# TC377TP_2.net
KiCad netlist of a schematic drawn in Altium Designer
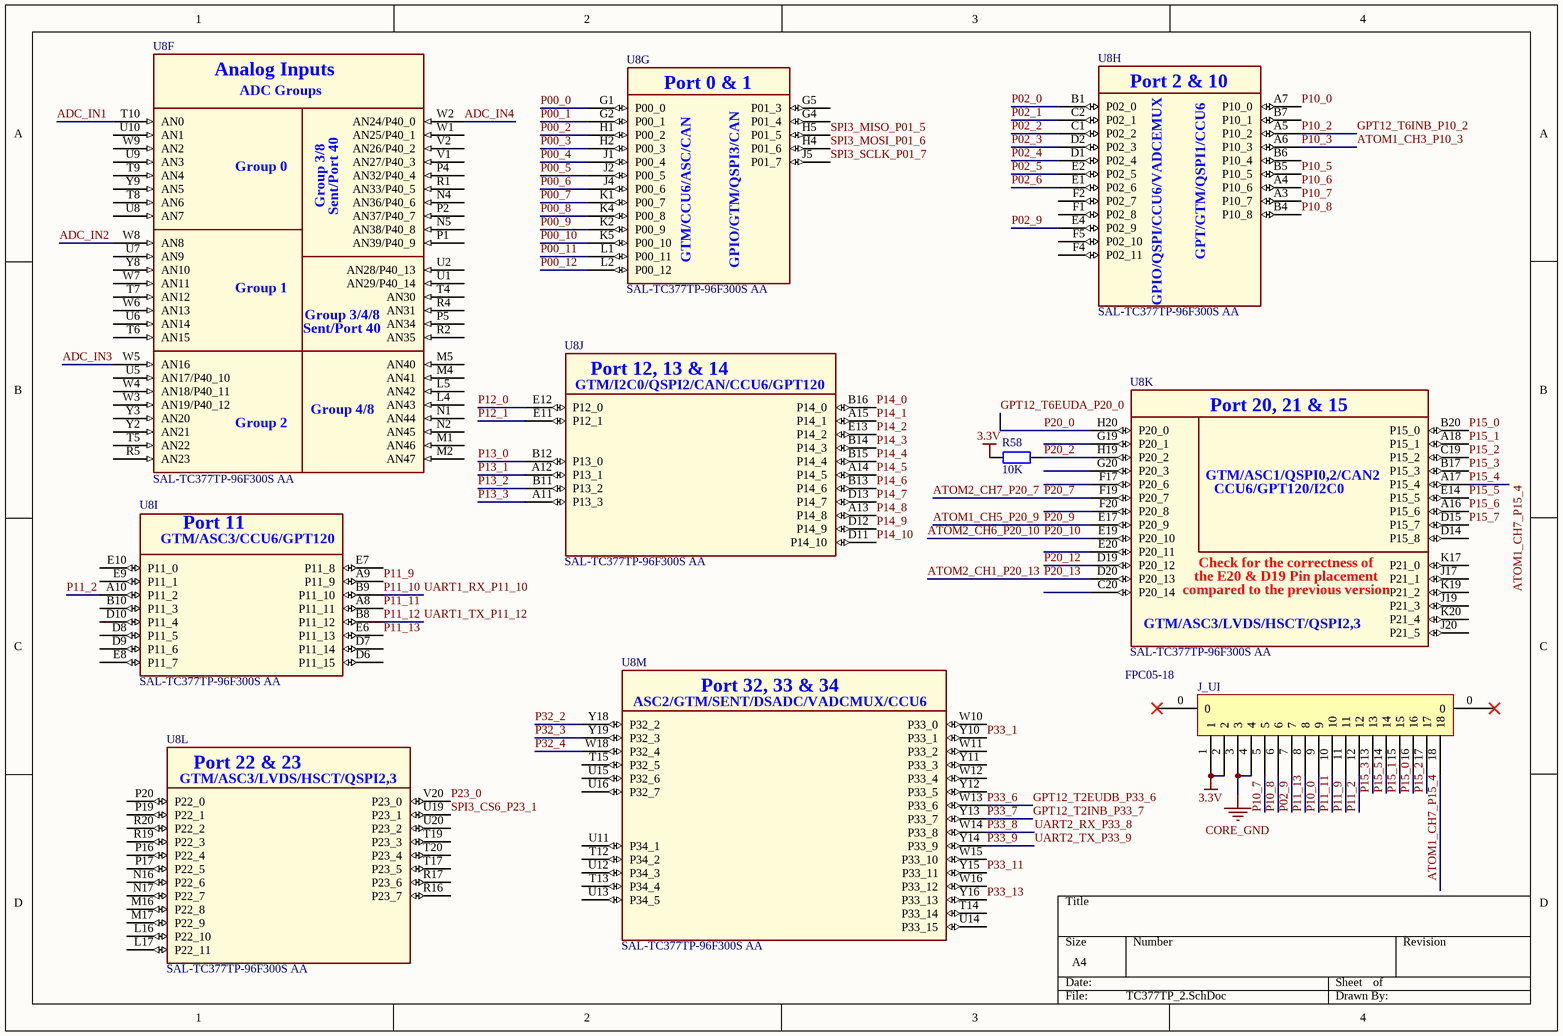
[diagram p0: TC377TP_2.SchDoc]

(export (version "E")
  (design (tool "Eeschema 10.0.6"))
  (components
    (comp (ref "J_UI")
      (value "FPC05-18")
      (footprint "FPC-05mm-18")
      (libsource (lib "FPC18") (part "FPC05-18"))
    )
    (comp (ref "R58")
      (value "10K")
      (footprint "R 0603_L")
      (description "贴片电阻")
      (fields (field (name "版权归属") "源创客"))
      (libsource (lib "3.1   - 电阻-电容-电感") (part "R"))
    )
    (comp (ref "U8")
      (value "SAL-TC377TP-96F300S AA")
      (footprint "BGA292C80P20X20")
      (description "32-Bit Single-Chip Microcontroller")
      (fields (field (name "MANUFACTURER") "Infineon Technologies"))
      (libsource (lib "SAL-TC377TP-96F300S AA") (part "SAL-TC377TP-96F300S AA"))
    )
  )
  (nets
    (net (code "1") (name "/ADC_IN1") (class "Default")
      (node (ref "U8") (pin "T10") (pinfunction "AN0_T10") (pintype "input"))
    )
    (net (code "2") (name "/ADC_IN2") (class "Default")
      (node (ref "U8") (pin "W8") (pinfunction "AN8_W8") (pintype "input"))
    )
    (net (code "3") (name "/ADC_IN3") (class "Default")
      (node (ref "U8") (pin "W5") (pinfunction "AN16_W5") (pintype "input"))
    )
    (net (code "4") (name "/ADC_IN4") (class "Default")
      (node (ref "U8") (pin "W2") (pinfunction "AN24/P40_0_W2") (pintype "input"))
    )
    (net (code "5") (name "/ATOM1_CH3_P10_3") (class "Default")
      (node (ref "U8") (pin "A6") (pinfunction "P10_3_A6") (pintype "bidirectional"))
    )
    (net (code "6") (name "/ATOM1_CH5_P20_9") (class "Default")
      (node (ref "U8") (pin "E17") (pinfunction "P20_9_E17") (pintype "bidirectional"))
    )
    (net (code "7") (name "/ATOM1_CH7_P15_4") (class "Default")
      (node (ref "J_UI") (pin "18") (pinfunction "18_18") (pintype "passive"))
      (node (ref "U8") (pin "A17") (pinfunction "P15_4_A17") (pintype "bidirectional"))
    )
    (net (code "8") (name "/ATOM2_CH1_P20_13") (class "Default")
      (node (ref "U8") (pin "D20") (pinfunction "P20_13_D20") (pintype "bidirectional"))
    )
    (net (code "9") (name "/ATOM2_CH6_P20_10") (class "Default")
      (node (ref "U8") (pin "E19") (pinfunction "P20_10_E19") (pintype "bidirectional"))
    )
    (net (code "10") (name "/ATOM2_CH7_P20_7") (class "Default")
      (node (ref "U8") (pin "F19") (pinfunction "P20_7_F19") (pintype "bidirectional"))
    )
    (net (code "11") (name "/GPT12_T2EUDB_P33_6") (class "Default")
      (node (ref "U8") (pin "W13") (pinfunction "P33_6_W13") (pintype "bidirectional"))
    )
    (net (code "12") (name "/GPT12_T2INB_P33_7") (class "Default")
      (node (ref "U8") (pin "Y13") (pinfunction "P33_7_Y13") (pintype "bidirectional"))
    )
    (net (code "13") (name "/GPT12_T6EUDA_P20_0") (class "Default")
      (node (ref "U8") (pin "H20") (pinfunction "P20_0_H20") (pintype "bidirectional"))
    )
    (net (code "14") (name "/GPT12_T6INB_P10_2") (class "Default")
      (node (ref "U8") (pin "A5") (pinfunction "P10_2_A5") (pintype "bidirectional"))
    )
    (net (code "15") (name "/P00_0") (class "Default")
      (node (ref "U8") (pin "G1") (pinfunction "P00_0_G1") (pintype "bidirectional"))
    )
    (net (code "16") (name "/P00_1") (class "Default")
      (node (ref "U8") (pin "G2") (pinfunction "P00_1_G2") (pintype "bidirectional"))
    )
    (net (code "17") (name "/P00_2") (class "Default")
      (node (ref "U8") (pin "H1") (pinfunction "P00_2_H1") (pintype "bidirectional"))
    )
    (net (code "18") (name "/P00_3") (class "Default")
      (node (ref "U8") (pin "H2") (pinfunction "P00_3_H2") (pintype "bidirectional"))
    )
    (net (code "19") (name "/P00_4") (class "Default")
      (node (ref "U8") (pin "J1") (pinfunction "P00_4_J1") (pintype "bidirectional"))
    )
    (net (code "20") (name "/P00_5") (class "Default")
      (node (ref "U8") (pin "J2") (pinfunction "P00_5_J2") (pintype "bidirectional"))
    )
    (net (code "21") (name "/P00_6") (class "Default")
      (node (ref "U8") (pin "J4") (pinfunction "P00_6_J4") (pintype "bidirectional"))
    )
    (net (code "22") (name "/P00_7") (class "Default")
      (node (ref "U8") (pin "K1") (pinfunction "P00_7_K1") (pintype "bidirectional"))
    )
    (net (code "23") (name "/P00_8") (class "Default")
      (node (ref "U8") (pin "K4") (pinfunction "P00_8_K4") (pintype "bidirectional"))
    )
    (net (code "24") (name "/P00_9") (class "Default")
      (node (ref "U8") (pin "K2") (pinfunction "P00_9_K2") (pintype "bidirectional"))
    )
    (net (code "25") (name "/P00_10") (class "Default")
      (node (ref "U8") (pin "K5") (pinfunction "P00_10_K5") (pintype "bidirectional"))
    )
    (net (code "26") (name "/P00_11") (class "Default")
      (node (ref "U8") (pin "L1") (pinfunction "P00_11_L1") (pintype "bidirectional"))
    )
    (net (code "27") (name "/P00_12") (class "Default")
      (node (ref "U8") (pin "L2") (pinfunction "P00_12_L2") (pintype "bidirectional"))
    )
    (net (code "28") (name "/P02_0") (class "Default")
      (node (ref "U8") (pin "B1") (pinfunction "P02_0_B1") (pintype "bidirectional"))
    )
    (net (code "29") (name "/P02_1") (class "Default")
      (node (ref "U8") (pin "C2") (pinfunction "P02_1_C2") (pintype "bidirectional"))
    )
    (net (code "30") (name "/P02_2") (class "Default")
      (node (ref "U8") (pin "C1") (pinfunction "P02_2_C1") (pintype "bidirectional"))
    )
    (net (code "31") (name "/P02_3") (class "Default")
      (node (ref "U8") (pin "D2") (pinfunction "P02_3_D2") (pintype "bidirectional"))
    )
    (net (code "32") (name "/P02_4") (class "Default")
      (node (ref "U8") (pin "D1") (pinfunction "P02_4_D1") (pintype "bidirectional"))
    )
    (net (code "33") (name "/P02_5") (class "Default")
      (node (ref "U8") (pin "E2") (pinfunction "P02_5_E2") (pintype "bidirectional"))
    )
    (net (code "34") (name "/P02_6") (class "Default")
      (node (ref "U8") (pin "E1") (pinfunction "P02_6_E1") (pintype "bidirectional"))
    )
    (net (code "35") (name "/P02_9") (class "Default")
      (node (ref "J_UI") (pin "7") (pinfunction "7_7") (pintype "passive"))
      (node (ref "U8") (pin "E4") (pinfunction "P02_9_E4") (pintype "bidirectional"))
    )
    (net (code "36") (name "/P10_0") (class "Default")
      (node (ref "J_UI") (pin "9") (pinfunction "9_9") (pintype "passive"))
      (node (ref "U8") (pin "A7") (pinfunction "P10_0_A7") (pintype "bidirectional"))
    )
    (net (code "37") (name "/P10_5") (class "Default")
      (node (ref "U8") (pin "B5") (pinfunction "P10_5_B5") (pintype "bidirectional"))
    )
    (net (code "38") (name "/P10_6") (class "Default")
      (node (ref "U8") (pin "A4") (pinfunction "P10_6_A4") (pintype "bidirectional"))
    )
    (net (code "39") (name "/P10_7") (class "Default")
      (node (ref "J_UI") (pin "5") (pinfunction "5_5") (pintype "passive"))
      (node (ref "U8") (pin "A3") (pinfunction "P10_7_A3") (pintype "bidirectional"))
    )
    (net (code "40") (name "/P10_8") (class "Default")
      (node (ref "J_UI") (pin "6") (pinfunction "6_6") (pintype "passive"))
      (node (ref "U8") (pin "B4") (pinfunction "P10_8_B4") (pintype "bidirectional"))
    )
    (net (code "41") (name "/P11_2") (class "Default")
      (node (ref "J_UI") (pin "12") (pinfunction "12_12") (pintype "passive"))
      (node (ref "U8") (pin "A10") (pinfunction "P11_2_A10") (pintype "bidirectional"))
    )
    (net (code "42") (name "/P11_9") (class "Default")
      (node (ref "J_UI") (pin "11") (pinfunction "11_11") (pintype "passive"))
      (node (ref "U8") (pin "A9") (pinfunction "P11_9_A9") (pintype "bidirectional"))
    )
    (net (code "43") (name "/P11_10") (class "Default")
      (node (ref "U8") (pin "B9") (pinfunction "P11_10_B9") (pintype "bidirectional"))
    )
    (net (code "44") (name "/P11_11") (class "Default")
      (node (ref "J_UI") (pin "10") (pinfunction "10_10") (pintype "passive"))
      (node (ref "U8") (pin "A8") (pinfunction "P11_11_A8") (pintype "bidirectional"))
    )
    (net (code "45") (name "/P11_12") (class "Default")
      (node (ref "U8") (pin "B8") (pinfunction "P11_12_B8") (pintype "bidirectional"))
    )
    (net (code "46") (name "/P11_13") (class "Default")
      (node (ref "J_UI") (pin "8") (pinfunction "8_8") (pintype "passive"))
      (node (ref "U8") (pin "E6") (pinfunction "P11_13_E6") (pintype "bidirectional"))
    )
    (net (code "47") (name "/P12_0") (class "Default")
      (node (ref "U8") (pin "E12") (pinfunction "P12_0_E12") (pintype "bidirectional"))
    )
    (net (code "48") (name "/P12_1") (class "Default")
      (node (ref "U8") (pin "E11") (pinfunction "P12_1_E11") (pintype "bidirectional"))
    )
    (net (code "49") (name "/P13_0") (class "Default")
      (node (ref "U8") (pin "B12") (pinfunction "P13_0_B12") (pintype "bidirectional"))
    )
    (net (code "50") (name "/P13_1") (class "Default")
      (node (ref "U8") (pin "A12") (pinfunction "P13_1_A12") (pintype "bidirectional"))
    )
    (net (code "51") (name "/P13_2") (class "Default")
      (node (ref "U8") (pin "B11") (pinfunction "P13_2_B11") (pintype "bidirectional"))
    )
    (net (code "52") (name "/P13_3") (class "Default")
      (node (ref "U8") (pin "A11") (pinfunction "P13_3_A11") (pintype "bidirectional"))
    )
    (net (code "53") (name "/P14_0") (class "Default")
      (node (ref "U8") (pin "B16") (pinfunction "P14_0_B16") (pintype "bidirectional"))
    )
    (net (code "54") (name "/P14_1") (class "Default")
      (node (ref "U8") (pin "A15") (pinfunction "P14_1_A15") (pintype "bidirectional"))
    )
    (net (code "55") (name "/P14_2") (class "Default")
      (node (ref "U8") (pin "E13") (pinfunction "P14_2_E13") (pintype "bidirectional"))
    )
    (net (code "56") (name "/P14_3") (class "Default")
      (node (ref "U8") (pin "B14") (pinfunction "P14_3_B14") (pintype "bidirectional"))
    )
    (net (code "57") (name "/P14_4") (class "Default")
      (node (ref "U8") (pin "B15") (pinfunction "P14_4_B15") (pintype "bidirectional"))
    )
    (net (code "58") (name "/P14_5") (class "Default")
      (node (ref "U8") (pin "A14") (pinfunction "P14_5_A14") (pintype "bidirectional"))
    )
    (net (code "59") (name "/P14_6") (class "Default")
      (node (ref "U8") (pin "B13") (pinfunction "P14_6_B13") (pintype "bidirectional"))
    )
    (net (code "60") (name "/P14_7") (class "Default")
      (node (ref "U8") (pin "D13") (pinfunction "P14_7_D13") (pintype "bidirectional"))
    )
    (net (code "61") (name "/P14_8") (class "Default")
      (node (ref "U8") (pin "A13") (pinfunction "P14_8_A13") (pintype "bidirectional"))
    )
    (net (code "62") (name "/P14_9") (class "Default")
      (node (ref "U8") (pin "D12") (pinfunction "P14_9_D12") (pintype "bidirectional"))
    )
    (net (code "63") (name "/P14_10") (class "Default")
      (node (ref "U8") (pin "D11") (pinfunction "P14_10_D11") (pintype "bidirectional"))
    )
    (net (code "64") (name "/P15_0") (class "Default")
      (node (ref "J_UI") (pin "16") (pinfunction "16_16") (pintype "passive"))
      (node (ref "U8") (pin "B20") (pinfunction "P15_0_B20") (pintype "bidirectional"))
    )
    (net (code "65") (name "/P15_1") (class "Default")
      (node (ref "J_UI") (pin "15") (pinfunction "15_15") (pintype "passive"))
      (node (ref "U8") (pin "A18") (pinfunction "P15_1_A18") (pintype "bidirectional"))
    )
    (net (code "66") (name "/P15_2") (class "Default")
      (node (ref "J_UI") (pin "17") (pinfunction "17_17") (pintype "passive"))
      (node (ref "U8") (pin "C19") (pinfunction "P15_2_C19") (pintype "bidirectional"))
    )
    (net (code "67") (name "/P15_3") (class "Default")
      (node (ref "J_UI") (pin "13") (pinfunction "13_13") (pintype "passive"))
      (node (ref "U8") (pin "B17") (pinfunction "P15_3_B17") (pintype "bidirectional"))
    )
    (net (code "68") (name "/P15_5") (class "Default")
      (node (ref "J_UI") (pin "14") (pinfunction "14_14") (pintype "passive"))
      (node (ref "U8") (pin "E14") (pinfunction "P15_5_E14") (pintype "bidirectional"))
    )
    (net (code "69") (name "/P15_6") (class "Default")
      (node (ref "U8") (pin "A16") (pinfunction "P15_6_A16") (pintype "bidirectional"))
    )
    (net (code "70") (name "/P15_7") (class "Default")
      (node (ref "U8") (pin "D15") (pinfunction "P15_7_D15") (pintype "bidirectional"))
    )
    (net (code "71") (name "/P20_2") (class "Default")
      (node (ref "R58") (pin "1") (pinfunction "1_1") (pintype "passive"))
      (node (ref "U8") (pin "H19") (pinfunction "P20_2_H19") (pintype "bidirectional"))
    )
    (net (code "72") (name "/P20_12") (class "Default")
      (node (ref "U8") (pin "D19") (pinfunction "P20_12_D19") (pintype "bidirectional"))
    )
    (net (code "73") (name "/P23_0") (class "Default")
      (node (ref "U8") (pin "V20") (pinfunction "P23_0_V20") (pintype "bidirectional"))
    )
    (net (code "74") (name "/P32_2") (class "Default")
      (node (ref "U8") (pin "Y18") (pinfunction "P32_2_Y18") (pintype "bidirectional"))
    )
    (net (code "75") (name "/P32_3") (class "Default")
      (node (ref "U8") (pin "Y19") (pinfunction "P32_3_Y19") (pintype "bidirectional"))
    )
    (net (code "76") (name "/P32_4") (class "Default")
      (node (ref "U8") (pin "W18") (pinfunction "P32_4_W18") (pintype "bidirectional"))
    )
    (net (code "77") (name "/P33_1") (class "Default")
      (node (ref "U8") (pin "Y10") (pinfunction "P33_1_Y10") (pintype "bidirectional"))
    )
    (net (code "78") (name "/P33_8") (class "Default")
      (node (ref "U8") (pin "W14") (pinfunction "P33_8_W14") (pintype "bidirectional"))
    )
    (net (code "79") (name "/P33_9") (class "Default")
      (node (ref "U8") (pin "Y14") (pinfunction "P33_9_Y14") (pintype "bidirectional"))
    )
    (net (code "80") (name "/P33_11") (class "Default")
      (node (ref "U8") (pin "Y15") (pinfunction "P33_11_Y15") (pintype "bidirectional"))
    )
    (net (code "81") (name "/P33_13") (class "Default")
      (node (ref "U8") (pin "Y16") (pinfunction "P33_13_Y16") (pintype "bidirectional"))
    )
    (net (code "82") (name "/SPI3_CS6_P23_1") (class "Default")
      (node (ref "U8") (pin "U19") (pinfunction "P23_1_U19") (pintype "bidirectional"))
    )
    (net (code "83") (name "/SPI3_MISO_P01_5") (class "Default")
      (node (ref "U8") (pin "H5") (pinfunction "P01_5_H5") (pintype "bidirectional"))
    )
    (net (code "84") (name "/SPI3_MOSI_P01_6") (class "Default")
      (node (ref "U8") (pin "H4") (pinfunction "P01_6_H4") (pintype "bidirectional"))
    )
    (net (code "85") (name "/SPI3_SCLK_P01_7") (class "Default")
      (node (ref "U8") (pin "J5") (pinfunction "P01_7_J5") (pintype "bidirectional"))
    )
    (net (code "86") (name "3.3V") (class "Default")
      (node (ref "J_UI") (pin "1") (pinfunction "1_1") (pintype "passive"))
      (node (ref "J_UI") (pin "2") (pinfunction "2_2") (pintype "passive"))
      (node (ref "R58") (pin "2") (pinfunction "2_2") (pintype "passive"))
    )
    (net (code "87") (name "CORE_GND") (class "Default")
      (node (ref "J_UI") (pin "3") (pinfunction "3_3") (pintype "passive"))
      (node (ref "J_UI") (pin "4") (pinfunction "4_4") (pintype "passive"))
    )
    (net (code "88") (name "unconnected-(J_UI-Pad0)") (class "Default")
      (node (ref "J_UI") (pin "0") (pinfunction "0_0") (pintype "passive+no_connect"))
    )
    (net (code "89") (name "unconnected-(J_UI-Pad0)_1") (class "Default")
      (node (ref "J_UI") (pin "0") (pinfunction "0_0") (pintype "passive+no_connect"))
    )
    (net (code "90") (name "unconnected-(U8F-AN1-PadU10)") (class "Default")
      (node (ref "U8") (pin "U10") (pinfunction "AN1_U10") (pintype "input"))
    )
    (net (code "91") (name "unconnected-(U8F-AN2-PadW9)") (class "Default")
      (node (ref "U8") (pin "W9") (pinfunction "AN2_W9") (pintype "input"))
    )
    (net (code "92") (name "unconnected-(U8F-AN3-PadU9)") (class "Default")
      (node (ref "U8") (pin "U9") (pinfunction "AN3_U9") (pintype "input"))
    )
    (net (code "93") (name "unconnected-(U8F-AN4-PadT9)") (class "Default")
      (node (ref "U8") (pin "T9") (pinfunction "AN4_T9") (pintype "input"))
    )
    (net (code "94") (name "unconnected-(U8F-AN5-PadY9)") (class "Default")
      (node (ref "U8") (pin "Y9") (pinfunction "AN5_Y9") (pintype "input"))
    )
    (net (code "95") (name "unconnected-(U8F-AN6-PadT8)") (class "Default")
      (node (ref "U8") (pin "T8") (pinfunction "AN6_T8") (pintype "input"))
    )
    (net (code "96") (name "unconnected-(U8F-AN7-PadU8)") (class "Default")
      (node (ref "U8") (pin "U8") (pinfunction "AN7_U8") (pintype "input"))
    )
    (net (code "97") (name "unconnected-(U8F-AN9-PadU7)") (class "Default")
      (node (ref "U8") (pin "U7") (pinfunction "AN9_U7") (pintype "input"))
    )
    (net (code "98") (name "unconnected-(U8F-AN10-PadY8)") (class "Default")
      (node (ref "U8") (pin "Y8") (pinfunction "AN10_Y8") (pintype "input"))
    )
    (net (code "99") (name "unconnected-(U8F-AN11-PadW7)") (class "Default")
      (node (ref "U8") (pin "W7") (pinfunction "AN11_W7") (pintype "input"))
    )
    (net (code "100") (name "unconnected-(U8F-AN12-PadT7)") (class "Default")
      (node (ref "U8") (pin "T7") (pinfunction "AN12_T7") (pintype "input"))
    )
    (net (code "101") (name "unconnected-(U8F-AN13-PadW6)") (class "Default")
      (node (ref "U8") (pin "W6") (pinfunction "AN13_W6") (pintype "input"))
    )
    (net (code "102") (name "unconnected-(U8F-AN14-PadU6)") (class "Default")
      (node (ref "U8") (pin "U6") (pinfunction "AN14_U6") (pintype "input"))
    )
    (net (code "103") (name "unconnected-(U8F-AN15-PadT6)") (class "Default")
      (node (ref "U8") (pin "T6") (pinfunction "AN15_T6") (pintype "input"))
    )
    (net (code "104") (name "unconnected-(U8F-AN17{slash}P40_10-PadU5)") (class "Default")
      (node (ref "U8") (pin "U5") (pinfunction "AN17/P40_10_U5") (pintype "input"))
    )
    (net (code "105") (name "unconnected-(U8F-AN18{slash}P40_11-PadW4)") (class "Default")
      (node (ref "U8") (pin "W4") (pinfunction "AN18/P40_11_W4") (pintype "input"))
    )
    (net (code "106") (name "unconnected-(U8F-AN19{slash}P40_12-PadW3)") (class "Default")
      (node (ref "U8") (pin "W3") (pinfunction "AN19/P40_12_W3") (pintype "input"))
    )
    (net (code "107") (name "unconnected-(U8F-AN20-PadY3)") (class "Default")
      (node (ref "U8") (pin "Y3") (pinfunction "AN20_Y3") (pintype "input"))
    )
    (net (code "108") (name "unconnected-(U8F-AN21-PadY2)") (class "Default")
      (node (ref "U8") (pin "Y2") (pinfunction "AN21_Y2") (pintype "input"))
    )
    (net (code "109") (name "unconnected-(U8F-AN22-PadT5)") (class "Default")
      (node (ref "U8") (pin "T5") (pinfunction "AN22_T5") (pintype "input"))
    )
    (net (code "110") (name "unconnected-(U8F-AN23-PadR5)") (class "Default")
      (node (ref "U8") (pin "R5") (pinfunction "AN23_R5") (pintype "input"))
    )
    (net (code "111") (name "unconnected-(U8F-AN25{slash}P40_1-PadW1)") (class "Default")
      (node (ref "U8") (pin "W1") (pinfunction "AN25/P40_1_W1") (pintype "input"))
    )
    (net (code "112") (name "unconnected-(U8F-AN26{slash}P40_2-PadV2)") (class "Default")
      (node (ref "U8") (pin "V2") (pinfunction "AN26/P40_2_V2") (pintype "input"))
    )
    (net (code "113") (name "unconnected-(U8F-AN27{slash}P40_3-PadV1)") (class "Default")
      (node (ref "U8") (pin "V1") (pinfunction "AN27/P40_3_V1") (pintype "input"))
    )
    (net (code "114") (name "unconnected-(U8F-AN28{slash}P40_13-PadU2)") (class "Default")
      (node (ref "U8") (pin "U2") (pinfunction "AN28/P40_13_U2") (pintype "input"))
    )
    (net (code "115") (name "unconnected-(U8F-AN29{slash}P40_14-PadU1)") (class "Default")
      (node (ref "U8") (pin "U1") (pinfunction "AN29/P40_14_U1") (pintype "input"))
    )
    (net (code "116") (name "unconnected-(U8F-AN30-PadT4)") (class "Default")
      (node (ref "U8") (pin "T4") (pinfunction "AN30_T4") (pintype "input"))
    )
    (net (code "117") (name "unconnected-(U8F-AN31-PadR4)") (class "Default")
      (node (ref "U8") (pin "R4") (pinfunction "AN31_R4") (pintype "input"))
    )
    (net (code "118") (name "unconnected-(U8F-AN32{slash}P40_4-PadP4)") (class "Default")
      (node (ref "U8") (pin "P4") (pinfunction "AN32/P40_4_P4") (pintype "input"))
    )
    (net (code "119") (name "unconnected-(U8F-AN33{slash}P40_5-PadR1)") (class "Default")
      (node (ref "U8") (pin "R1") (pinfunction "AN33/P40_5_R1") (pintype "input"))
    )
    (net (code "120") (name "unconnected-(U8F-AN34-PadP5)") (class "Default")
      (node (ref "U8") (pin "P5") (pinfunction "AN34_P5") (pintype "input"))
    )
    (net (code "121") (name "unconnected-(U8F-AN35-PadR2)") (class "Default")
      (node (ref "U8") (pin "R2") (pinfunction "AN35_R2") (pintype "input"))
    )
    (net (code "122") (name "unconnected-(U8F-AN36{slash}P40_6-PadN4)") (class "Default")
      (node (ref "U8") (pin "N4") (pinfunction "AN36/P40_6_N4") (pintype "input"))
    )
    (net (code "123") (name "unconnected-(U8F-AN37{slash}P40_7-PadP2)") (class "Default")
      (node (ref "U8") (pin "P2") (pinfunction "AN37/P40_7_P2") (pintype "input"))
    )
    (net (code "124") (name "unconnected-(U8F-AN38{slash}P40_8-PadN5)") (class "Default")
      (node (ref "U8") (pin "N5") (pinfunction "AN38/P40_8_N5") (pintype "input"))
    )
    (net (code "125") (name "unconnected-(U8F-AN39{slash}P40_9-PadP1)") (class "Default")
      (node (ref "U8") (pin "P1") (pinfunction "AN39/P40_9_P1") (pintype "input"))
    )
    (net (code "126") (name "unconnected-(U8F-AN40-PadM5)") (class "Default")
      (node (ref "U8") (pin "M5") (pinfunction "AN40_M5") (pintype "input"))
    )
    (net (code "127") (name "unconnected-(U8F-AN41-PadM4)") (class "Default")
      (node (ref "U8") (pin "M4") (pinfunction "AN41_M4") (pintype "input"))
    )
    (net (code "128") (name "unconnected-(U8F-AN42-PadL5)") (class "Default")
      (node (ref "U8") (pin "L5") (pinfunction "AN42_L5") (pintype "input"))
    )
    (net (code "129") (name "unconnected-(U8F-AN43-PadL4)") (class "Default")
      (node (ref "U8") (pin "L4") (pinfunction "AN43_L4") (pintype "input"))
    )
    (net (code "130") (name "unconnected-(U8F-AN44-PadN1)") (class "Default")
      (node (ref "U8") (pin "N1") (pinfunction "AN44_N1") (pintype "input"))
    )
    (net (code "131") (name "unconnected-(U8F-AN45-PadN2)") (class "Default")
      (node (ref "U8") (pin "N2") (pinfunction "AN45_N2") (pintype "input"))
    )
    (net (code "132") (name "unconnected-(U8F-AN46-PadM1)") (class "Default")
      (node (ref "U8") (pin "M1") (pinfunction "AN46_M1") (pintype "input"))
    )
    (net (code "133") (name "unconnected-(U8F-AN47-PadM2)") (class "Default")
      (node (ref "U8") (pin "M2") (pinfunction "AN47_M2") (pintype "input"))
    )
    (net (code "134") (name "unconnected-(U8G-P01_3-PadG5)") (class "Default")
      (node (ref "U8") (pin "G5") (pinfunction "P01_3_G5") (pintype "bidirectional"))
    )
    (net (code "135") (name "unconnected-(U8G-P01_4-PadG4)") (class "Default")
      (node (ref "U8") (pin "G4") (pinfunction "P01_4_G4") (pintype "bidirectional"))
    )
    (net (code "136") (name "unconnected-(U8H-P02_7-PadF2)") (class "Default")
      (node (ref "U8") (pin "F2") (pinfunction "P02_7_F2") (pintype "bidirectional"))
    )
    (net (code "137") (name "unconnected-(U8H-P02_8-PadF1)") (class "Default")
      (node (ref "U8") (pin "F1") (pinfunction "P02_8_F1") (pintype "bidirectional"))
    )
    (net (code "138") (name "unconnected-(U8H-P02_10-PadF5)") (class "Default")
      (node (ref "U8") (pin "F5") (pinfunction "P02_10_F5") (pintype "bidirectional"))
    )
    (net (code "139") (name "unconnected-(U8H-P02_11-PadF4)") (class "Default")
      (node (ref "U8") (pin "F4") (pinfunction "P02_11_F4") (pintype "bidirectional"))
    )
    (net (code "140") (name "unconnected-(U8H-P10_1-PadB7)") (class "Default")
      (node (ref "U8") (pin "B7") (pinfunction "P10_1_B7") (pintype "bidirectional"))
    )
    (net (code "141") (name "unconnected-(U8H-P10_4-PadB6)") (class "Default")
      (node (ref "U8") (pin "B6") (pinfunction "P10_4_B6") (pintype "bidirectional"))
    )
    (net (code "142") (name "unconnected-(U8I-P11_0-PadE10)") (class "Default")
      (node (ref "U8") (pin "E10") (pinfunction "P11_0_E10") (pintype "bidirectional"))
    )
    (net (code "143") (name "unconnected-(U8I-P11_1-PadE9)") (class "Default")
      (node (ref "U8") (pin "E9") (pinfunction "P11_1_E9") (pintype "bidirectional"))
    )
    (net (code "144") (name "unconnected-(U8I-P11_3-PadB10)") (class "Default")
      (node (ref "U8") (pin "B10") (pinfunction "P11_3_B10") (pintype "bidirectional"))
    )
    (net (code "145") (name "unconnected-(U8I-P11_4-PadD10)") (class "Default")
      (node (ref "U8") (pin "D10") (pinfunction "P11_4_D10") (pintype "bidirectional"))
    )
    (net (code "146") (name "unconnected-(U8I-P11_5-PadD8)") (class "Default")
      (node (ref "U8") (pin "D8") (pinfunction "P11_5_D8") (pintype "bidirectional"))
    )
    (net (code "147") (name "unconnected-(U8I-P11_6-PadD9)") (class "Default")
      (node (ref "U8") (pin "D9") (pinfunction "P11_6_D9") (pintype "bidirectional"))
    )
    (net (code "148") (name "unconnected-(U8I-P11_7-PadE8)") (class "Default")
      (node (ref "U8") (pin "E8") (pinfunction "P11_7_E8") (pintype "bidirectional"))
    )
    (net (code "149") (name "unconnected-(U8I-P11_8-PadE7)") (class "Default")
      (node (ref "U8") (pin "E7") (pinfunction "P11_8_E7") (pintype "bidirectional"))
    )
    (net (code "150") (name "unconnected-(U8I-P11_14-PadD7)") (class "Default")
      (node (ref "U8") (pin "D7") (pinfunction "P11_14_D7") (pintype "bidirectional"))
    )
    (net (code "151") (name "unconnected-(U8I-P11_15-PadD6)") (class "Default")
      (node (ref "U8") (pin "D6") (pinfunction "P11_15_D6") (pintype "bidirectional"))
    )
    (net (code "152") (name "unconnected-(U8K-P15_8-PadD14)") (class "Default")
      (node (ref "U8") (pin "D14") (pinfunction "P15_8_D14") (pintype "bidirectional"))
    )
    (net (code "153") (name "unconnected-(U8K-P20_1-PadG19)") (class "Default")
      (node (ref "U8") (pin "G19") (pinfunction "P20_1_G19") (pintype "bidirectional"))
    )
    (net (code "154") (name "unconnected-(U8K-P20_3-PadG20)") (class "Default")
      (node (ref "U8") (pin "G20") (pinfunction "P20_3_G20") (pintype "bidirectional"))
    )
    (net (code "155") (name "unconnected-(U8K-P20_6-PadF17)") (class "Default")
      (node (ref "U8") (pin "F17") (pinfunction "P20_6_F17") (pintype "bidirectional"))
    )
    (net (code "156") (name "unconnected-(U8K-P20_8-PadF20)") (class "Default")
      (node (ref "U8") (pin "F20") (pinfunction "P20_8_F20") (pintype "bidirectional"))
    )
    (net (code "157") (name "unconnected-(U8K-P20_11-PadE20)") (class "Default")
      (node (ref "U8") (pin "E20") (pinfunction "P20_11_E20") (pintype "bidirectional"))
    )
    (net (code "158") (name "unconnected-(U8K-P20_14-PadC20)") (class "Default")
      (node (ref "U8") (pin "C20") (pinfunction "P20_14_C20") (pintype "bidirectional"))
    )
    (net (code "159") (name "unconnected-(U8K-P21_0-PadK17)") (class "Default")
      (node (ref "U8") (pin "K17") (pinfunction "P21_0_K17") (pintype "bidirectional"))
    )
    (net (code "160") (name "unconnected-(U8K-P21_1-PadJ17)") (class "Default")
      (node (ref "U8") (pin "J17") (pinfunction "P21_1_J17") (pintype "bidirectional"))
    )
    (net (code "161") (name "unconnected-(U8K-P21_2-PadK19)") (class "Default")
      (node (ref "U8") (pin "K19") (pinfunction "P21_2_K19") (pintype "bidirectional"))
    )
    (net (code "162") (name "unconnected-(U8K-P21_3-PadJ19)") (class "Default")
      (node (ref "U8") (pin "J19") (pinfunction "P21_3_J19") (pintype "bidirectional"))
    )
    (net (code "163") (name "unconnected-(U8K-P21_4-PadK20)") (class "Default")
      (node (ref "U8") (pin "K20") (pinfunction "P21_4_K20") (pintype "bidirectional"))
    )
    (net (code "164") (name "unconnected-(U8K-P21_5-PadJ20)") (class "Default")
      (node (ref "U8") (pin "J20") (pinfunction "P21_5_J20") (pintype "bidirectional"))
    )
    (net (code "165") (name "unconnected-(U8L-P22_0-PadP20)") (class "Default")
      (node (ref "U8") (pin "P20") (pinfunction "P22_0_P20") (pintype "bidirectional"))
    )
    (net (code "166") (name "unconnected-(U8L-P22_1-PadP19)") (class "Default")
      (node (ref "U8") (pin "P19") (pinfunction "P22_1_P19") (pintype "bidirectional"))
    )
    (net (code "167") (name "unconnected-(U8L-P22_2-PadR20)") (class "Default")
      (node (ref "U8") (pin "R20") (pinfunction "P22_2_R20") (pintype "bidirectional"))
    )
    (net (code "168") (name "unconnected-(U8L-P22_3-PadR19)") (class "Default")
      (node (ref "U8") (pin "R19") (pinfunction "P22_3_R19") (pintype "bidirectional"))
    )
    (net (code "169") (name "unconnected-(U8L-P22_4-PadP16)") (class "Default")
      (node (ref "U8") (pin "P16") (pinfunction "P22_4_P16") (pintype "bidirectional"))
    )
    (net (code "170") (name "unconnected-(U8L-P22_5-PadP17)") (class "Default")
      (node (ref "U8") (pin "P17") (pinfunction "P22_5_P17") (pintype "bidirectional"))
    )
    (net (code "171") (name "unconnected-(U8L-P22_6-PadN16)") (class "Default")
      (node (ref "U8") (pin "N16") (pinfunction "P22_6_N16") (pintype "bidirectional"))
    )
    (net (code "172") (name "unconnected-(U8L-P22_7-PadN17)") (class "Default")
      (node (ref "U8") (pin "N17") (pinfunction "P22_7_N17") (pintype "bidirectional"))
    )
    (net (code "173") (name "unconnected-(U8L-P22_8-PadM16)") (class "Default")
      (node (ref "U8") (pin "M16") (pinfunction "P22_8_M16") (pintype "bidirectional"))
    )
    (net (code "174") (name "unconnected-(U8L-P22_9-PadM17)") (class "Default")
      (node (ref "U8") (pin "M17") (pinfunction "P22_9_M17") (pintype "bidirectional"))
    )
    (net (code "175") (name "unconnected-(U8L-P22_10-PadL16)") (class "Default")
      (node (ref "U8") (pin "L16") (pinfunction "P22_10_L16") (pintype "bidirectional"))
    )
    (net (code "176") (name "unconnected-(U8L-P22_11-PadL17)") (class "Default")
      (node (ref "U8") (pin "L17") (pinfunction "P22_11_L17") (pintype "bidirectional"))
    )
    (net (code "177") (name "unconnected-(U8L-P23_2-PadU20)") (class "Default")
      (node (ref "U8") (pin "U20") (pinfunction "P23_2_U20") (pintype "bidirectional"))
    )
    (net (code "178") (name "unconnected-(U8L-P23_3-PadT19)") (class "Default")
      (node (ref "U8") (pin "T19") (pinfunction "P23_3_T19") (pintype "bidirectional"))
    )
    (net (code "179") (name "unconnected-(U8L-P23_4-PadT20)") (class "Default")
      (node (ref "U8") (pin "T20") (pinfunction "P23_4_T20") (pintype "bidirectional"))
    )
    (net (code "180") (name "unconnected-(U8L-P23_5-PadT17)") (class "Default")
      (node (ref "U8") (pin "T17") (pinfunction "P23_5_T17") (pintype "bidirectional"))
    )
    (net (code "181") (name "unconnected-(U8L-P23_6-PadR17)") (class "Default")
      (node (ref "U8") (pin "R17") (pinfunction "P23_6_R17") (pintype "bidirectional"))
    )
    (net (code "182") (name "unconnected-(U8L-P23_7-PadR16)") (class "Default")
      (node (ref "U8") (pin "R16") (pinfunction "P23_7_R16") (pintype "bidirectional"))
    )
    (net (code "183") (name "unconnected-(U8M-P32_5-PadT15)") (class "Default")
      (node (ref "U8") (pin "T15") (pinfunction "P32_5_T15") (pintype "bidirectional"))
    )
    (net (code "184") (name "unconnected-(U8M-P32_6-PadU15)") (class "Default")
      (node (ref "U8") (pin "U15") (pinfunction "P32_6_U15") (pintype "bidirectional"))
    )
    (net (code "185") (name "unconnected-(U8M-P32_7-PadU16)") (class "Default")
      (node (ref "U8") (pin "U16") (pinfunction "P32_7_U16") (pintype "bidirectional"))
    )
    (net (code "186") (name "unconnected-(U8M-P33_0-PadW10)") (class "Default")
      (node (ref "U8") (pin "W10") (pinfunction "P33_0_W10") (pintype "bidirectional"))
    )
    (net (code "187") (name "unconnected-(U8M-P33_2-PadW11)") (class "Default")
      (node (ref "U8") (pin "W11") (pinfunction "P33_2_W11") (pintype "bidirectional"))
    )
    (net (code "188") (name "unconnected-(U8M-P33_3-PadY11)") (class "Default")
      (node (ref "U8") (pin "Y11") (pinfunction "P33_3_Y11") (pintype "bidirectional"))
    )
    (net (code "189") (name "unconnected-(U8M-P33_4-PadW12)") (class "Default")
      (node (ref "U8") (pin "W12") (pinfunction "P33_4_W12") (pintype "bidirectional"))
    )
    (net (code "190") (name "unconnected-(U8M-P33_5-PadY12)") (class "Default")
      (node (ref "U8") (pin "Y12") (pinfunction "P33_5_Y12") (pintype "bidirectional"))
    )
    (net (code "191") (name "unconnected-(U8M-P33_10-PadW15)") (class "Default")
      (node (ref "U8") (pin "W15") (pinfunction "P33_10_W15") (pintype "bidirectional"))
    )
    (net (code "192") (name "unconnected-(U8M-P33_12-PadW16)") (class "Default")
      (node (ref "U8") (pin "W16") (pinfunction "P33_12_W16") (pintype "bidirectional"))
    )
    (net (code "193") (name "unconnected-(U8M-P33_14-PadT14)") (class "Default")
      (node (ref "U8") (pin "T14") (pinfunction "P33_14_T14") (pintype "bidirectional"))
    )
    (net (code "194") (name "unconnected-(U8M-P33_15-PadU14)") (class "Default")
      (node (ref "U8") (pin "U14") (pinfunction "P33_15_U14") (pintype "bidirectional"))
    )
    (net (code "195") (name "unconnected-(U8M-P34_1-PadU11)") (class "Default")
      (node (ref "U8") (pin "U11") (pinfunction "P34_1_U11") (pintype "bidirectional"))
    )
    (net (code "196") (name "unconnected-(U8M-P34_2-PadT12)") (class "Default")
      (node (ref "U8") (pin "T12") (pinfunction "P34_2_T12") (pintype "bidirectional"))
    )
    (net (code "197") (name "unconnected-(U8M-P34_3-PadU12)") (class "Default")
      (node (ref "U8") (pin "U12") (pinfunction "P34_3_U12") (pintype "bidirectional"))
    )
    (net (code "198") (name "unconnected-(U8M-P34_4-PadT13)") (class "Default")
      (node (ref "U8") (pin "T13") (pinfunction "P34_4_T13") (pintype "bidirectional"))
    )
    (net (code "199") (name "unconnected-(U8M-P34_5-PadU13)") (class "Default")
      (node (ref "U8") (pin "U13") (pinfunction "P34_5_U13") (pintype "bidirectional"))
    )
  )
)
